# power.net
KiCad netlist of a schematic drawn in Altium Designer
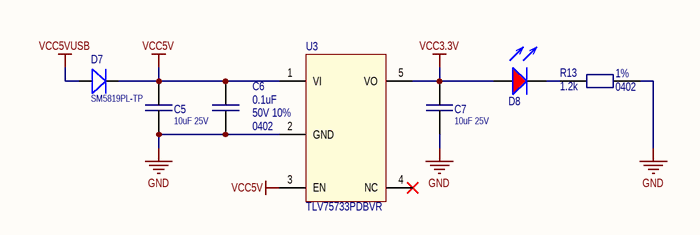
[diagram p0: power.SchDoc]

(export (version "E")
  (design (tool "Eeschema 10.0.6"))
  (components
    (comp (ref "C5")
      (value "10uF 25V")
      (footprint "C_0603")
      (description "Capacitor")
      (fields (field (name "PART") "CC0603MRX5R8BB106"))
      (libsource (lib "capacitors") (part "C0603"))
    )
    (comp (ref "C6")
      (value "0.1uF")
      (footprint "C_0402")
      (description "Capacitor")
      (fields
        (field (name "PART") "CC0402KRX5R9BB104")
        (field (name "CASE/PACKAGE") "0402")
        (field (name "TOLERANCE") "50V 10%")
        (field (name "Comment") "C0402")
      )
      (libsource (lib "capacitors") (part "C0402"))
    )
    (comp (ref "C7")
      (value "10uF 25V")
      (footprint "C_0603")
      (description "Capacitor")
      (fields (field (name "PART") "CC0603MRX5R8BB106"))
      (libsource (lib "capacitors") (part "C0603"))
    )
    (comp (ref "D7")
      (value "SM5819PL-TP")
      (footprint "SOD123FL")
      (description "Diode")
      (libsource (lib "diode") (part "D_SOD123"))
    )
    (comp (ref "D8")
      (value "Red 645nm")
      (footprint "LED 0603 RED, 60°")
      (description "RED LED 0603, 60°")
      (fields (field (name "PART") "APTD1608LSURCK"))
      (libsource (lib "led_lcd") (part "RED-LED-0603"))
    )
    (comp (ref "R13")
      (value "1.2k")
      (footprint "R_0402")
      (description "Resistor")
      (fields
        (field (name "PART") "RC0402FR-071K2L")
        (field (name "CASE/PACKAGE") "0402")
        (field (name "TOLERANCE") "1%")
        (field (name "Comment") "R0402")
      )
      (libsource (lib "resistors") (part "R0402"))
    )
    (comp (ref "U3")
      (value "TLV75733PDBVR")
      (footprint "SOT23-5")
      (description "Ultra-Low Quiescent Current LDO")
      (libsource (lib "dcdc_ldo_ref") (part "TPL720F33-5TR"))
    )
  )
  (nets
    (net (code "1") (name "GND") (class "Default")
      (node (ref "C5") (pin "1") (pinfunction "1_1") (pintype "passive"))
      (node (ref "C6") (pin "1") (pinfunction "1_1") (pintype "passive"))
      (node (ref "C7") (pin "1") (pinfunction "1_1") (pintype "passive"))
      (node (ref "R13") (pin "1") (pinfunction "1_1") (pintype "passive"))
      (node (ref "U3") (pin "2") (pinfunction "GND_2") (pintype "passive"))
    )
    (net (code "2") (name "Net-(D8-Pad1)") (class "Default")
      (node (ref "D8") (pin "1") (pinfunction "1_1") (pintype "passive"))
      (node (ref "R13") (pin "2") (pinfunction "2_2") (pintype "passive"))
    )
    (net (code "3") (name "VCC3.3V") (class "Default")
      (node (ref "C7") (pin "2") (pinfunction "2_2") (pintype "passive"))
      (node (ref "D8") (pin "2") (pinfunction "2_2") (pintype "passive"))
      (node (ref "U3") (pin "5") (pinfunction "VO_5") (pintype "passive"))
    )
    (net (code "4") (name "VCC5V") (class "Default")
      (node (ref "C5") (pin "2") (pinfunction "2_2") (pintype "passive"))
      (node (ref "C6") (pin "2") (pinfunction "2_2") (pintype "passive"))
      (node (ref "D7") (pin "2") (pinfunction "K_2") (pintype "passive"))
      (node (ref "U3") (pin "1") (pinfunction "VI_1") (pintype "passive"))
      (node (ref "U3") (pin "3") (pinfunction "EN_3") (pintype "passive"))
    )
    (net (code "5") (name "VCC5VUSB") (class "Default")
      (node (ref "D7") (pin "1") (pinfunction "A_1") (pintype "passive"))
    )
    (net (code "6") (name "unconnected-(U3-NC-Pad4)") (class "Default")
      (node (ref "U3") (pin "4") (pinfunction "NC_4") (pintype "passive+no_connect"))
    )
  )
)
